# power_adc_module.net
KiCad netlist of a schematic drawn in EAGLE
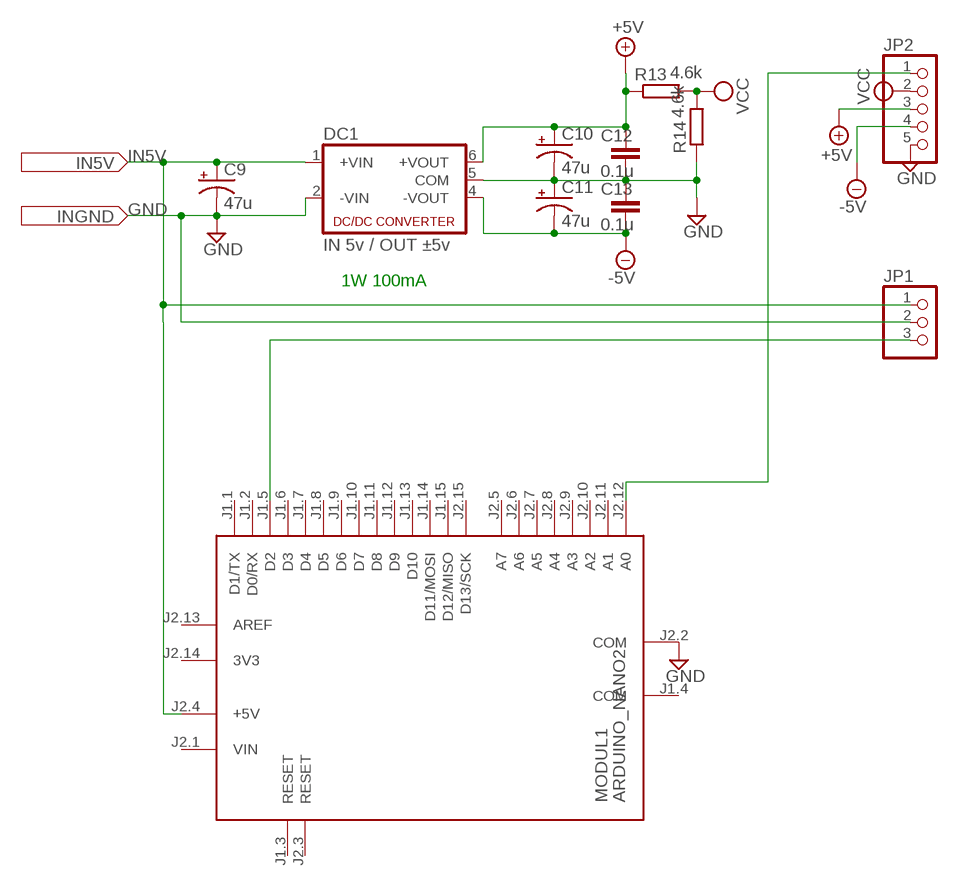
[diagram p0: schematic, sheet 1]

(export (version "E")
  (design (tool "Eeschema 10.0.6"))
  (components
    (comp (ref "C9")
      (value "47u")
      (footprint "eagle-import:E2,5-5")
      (libsource (lib "eagle-import") (part "CPOL-USE2.5-5"))
    )
    (comp (ref "C10")
      (value "47u")
      (footprint "eagle-import:E2,5-5")
      (libsource (lib "eagle-import") (part "CPOL-USE2.5-5"))
    )
    (comp (ref "C11")
      (value "47u")
      (footprint "eagle-import:E2,5-5")
      (libsource (lib "eagle-import") (part "CPOL-USE2.5-5"))
    )
    (comp (ref "C12")
      (value "0.1u")
      (footprint "eagle-import:C025-024X044")
      (libsource (lib "eagle-import") (part "C-EU025-024X044"))
    )
    (comp (ref "C13")
      (value "0.1u")
      (footprint "eagle-import:C025-024X044")
      (libsource (lib "eagle-import") (part "C-EU025-024X044"))
    )
    (comp (ref "DC1")
      (value "IN 5v / OUT ±5v")
      (footprint "eagle-import:NMA")
      (fields (field (name "MF") "C & D TECHNOLOGIES, INC") (field (name "MPN") "NMA0515SC"))
      (libsource (lib "eagle-import") (part "NMA"))
    )
    (comp (ref "JP1")
      (value "PINHD-1X3")
      (footprint "eagle-import:1X03")
      (libsource (lib "eagle-import") (part "PINHD-1X3"))
    )
    (comp (ref "JP2")
      (value "PINHD-1X5")
      (footprint "eagle-import:1X05")
      (libsource (lib "eagle-import") (part "PINHD-1X5"))
    )
    (comp (ref "MODUL1")
      (value "ARDUINO_NANO2")
      (footprint "eagle-import:ARDUINO_NANO2")
      (libsource (lib "eagle-import") (part "ARDUINO_NANO2"))
    )
    (comp (ref "R13")
      (value "4.6k")
      (footprint "eagle-import:0204_7")
      (libsource (lib "eagle-import") (part "R-EU_0204/7"))
    )
    (comp (ref "R14")
      (value "4.6k")
      (footprint "eagle-import:0204_7")
      (libsource (lib "eagle-import") (part "R-EU_0204/7"))
    )
  )
  (nets
    (net (code "1") (name "+5V") (class "Default")
      (node (ref "C10") (pin "+") (pinfunction "+_+") (pintype "passive"))
      (node (ref "C12") (pin "1") (pinfunction "1_1") (pintype "passive"))
      (node (ref "DC1") (pin "6") (pinfunction "+VOUT_6") (pintype "passive"))
      (node (ref "JP2") (pin "3") (pinfunction "3_3") (pintype "passive"))
      (node (ref "R13") (pin "1") (pinfunction "1_1") (pintype "passive"))
    )
    (net (code "2") (name "-5V") (class "Default")
      (node (ref "C11") (pin "-") (pinfunction "-_-") (pintype "passive"))
      (node (ref "C13") (pin "2") (pinfunction "2_2") (pintype "passive"))
      (node (ref "DC1") (pin "4") (pinfunction "-VOUT_4") (pintype "passive"))
      (node (ref "JP2") (pin "4") (pinfunction "4_4") (pintype "passive"))
    )
    (net (code "3") (name "/3V3") (class "Default")
      (node (ref "MODUL1") (pin "J2.14") (pinfunction "3V3_J2.14") (pintype "power_in"))
    )
    (net (code "4") (name "/AREF") (class "Default")
      (node (ref "MODUL1") (pin "J2.13") (pinfunction "AREF_J2.13") (pintype "power_in"))
    )
    (net (code "5") (name "/COM") (class "Default")
      (node (ref "MODUL1") (pin "J1.4") (pinfunction "COM_J1.4") (pintype "power_in"))
    )
    (net (code "6") (name "/IN5V") (class "Default")
      (node (ref "C9") (pin "+") (pinfunction "+_+") (pintype "passive"))
      (node (ref "DC1") (pin "1") (pinfunction "+VIN_1") (pintype "passive"))
      (node (ref "JP1") (pin "1") (pinfunction "1_1") (pintype "passive"))
      (node (ref "MODUL1") (pin "J2.4") (pinfunction "+5V_J2.4") (pintype "power_in"))
    )
    (net (code "7") (name "/VIN") (class "Default")
      (node (ref "MODUL1") (pin "J2.1") (pinfunction "VIN_J2.1") (pintype "power_in"))
    )
    (net (code "8") (name "GND") (class "Default")
      (node (ref "C10") (pin "-") (pinfunction "-_-") (pintype "passive"))
      (node (ref "C11") (pin "+") (pinfunction "+_+") (pintype "passive"))
      (node (ref "C12") (pin "2") (pinfunction "2_2") (pintype "passive"))
      (node (ref "C13") (pin "1") (pinfunction "1_1") (pintype "passive"))
      (node (ref "C9") (pin "-") (pinfunction "-_-") (pintype "passive"))
      (node (ref "DC1") (pin "2") (pinfunction "-VIN_2") (pintype "passive"))
      (node (ref "DC1") (pin "5") (pinfunction "COM_5") (pintype "passive"))
      (node (ref "JP1") (pin "2") (pinfunction "2_2") (pintype "passive"))
      (node (ref "JP2") (pin "5") (pinfunction "5_5") (pintype "passive"))
      (node (ref "MODUL1") (pin "J2.2") (pinfunction "COM_J2.2") (pintype "power_in"))
      (node (ref "R14") (pin "1") (pinfunction "1_1") (pintype "passive"))
    )
    (net (code "9") (name "Net-(MODUL1-A0)") (class "Default")
      (node (ref "JP2") (pin "1") (pinfunction "1_1") (pintype "passive"))
      (node (ref "MODUL1") (pin "J2.12") (pinfunction "A0_J2.12") (pintype "bidirectional"))
    )
    (net (code "10") (name "Net-(MODUL1-D2)") (class "Default")
      (node (ref "JP1") (pin "3") (pinfunction "3_3") (pintype "passive"))
      (node (ref "MODUL1") (pin "J1.5") (pinfunction "D2_J1.5") (pintype "bidirectional"))
    )
    (net (code "11") (name "VCC") (class "Default")
      (node (ref "JP2") (pin "2") (pinfunction "2_2") (pintype "passive"))
      (node (ref "R13") (pin "2") (pinfunction "2_2") (pintype "passive"))
      (node (ref "R14") (pin "2") (pinfunction "2_2") (pintype "passive"))
    )
    (net (code "12") (name "unconnected-(MODUL1-A1-PadJ2.11)") (class "Default")
      (node (ref "MODUL1") (pin "J2.11") (pinfunction "A1_J2.11") (pintype "bidirectional"))
    )
    (net (code "13") (name "unconnected-(MODUL1-A2-PadJ2.10)") (class "Default")
      (node (ref "MODUL1") (pin "J2.10") (pinfunction "A2_J2.10") (pintype "bidirectional"))
    )
    (net (code "14") (name "unconnected-(MODUL1-A3-PadJ2.9)") (class "Default")
      (node (ref "MODUL1") (pin "J2.9") (pinfunction "A3_J2.9") (pintype "bidirectional"))
    )
    (net (code "15") (name "unconnected-(MODUL1-A4-PadJ2.8)") (class "Default")
      (node (ref "MODUL1") (pin "J2.8") (pinfunction "A4_J2.8") (pintype "bidirectional"))
    )
    (net (code "16") (name "unconnected-(MODUL1-A5-PadJ2.7)") (class "Default")
      (node (ref "MODUL1") (pin "J2.7") (pinfunction "A5_J2.7") (pintype "bidirectional"))
    )
    (net (code "17") (name "unconnected-(MODUL1-A6-PadJ2.6)") (class "Default")
      (node (ref "MODUL1") (pin "J2.6") (pinfunction "A6_J2.6") (pintype "bidirectional"))
    )
    (net (code "18") (name "unconnected-(MODUL1-A7-PadJ2.5)") (class "Default")
      (node (ref "MODUL1") (pin "J2.5") (pinfunction "A7_J2.5") (pintype "bidirectional"))
    )
    (net (code "19") (name "unconnected-(MODUL1-D0{slash}RX-PadJ1.2)") (class "Default")
      (node (ref "MODUL1") (pin "J1.2") (pinfunction "D0/RX_J1.2") (pintype "bidirectional"))
    )
    (net (code "20") (name "unconnected-(MODUL1-D1{slash}TX-PadJ1.1)") (class "Default")
      (node (ref "MODUL1") (pin "J1.1") (pinfunction "D1/TX_J1.1") (pintype "bidirectional"))
    )
    (net (code "21") (name "unconnected-(MODUL1-D3-PadJ1.6)") (class "Default")
      (node (ref "MODUL1") (pin "J1.6") (pinfunction "D3_J1.6") (pintype "bidirectional"))
    )
    (net (code "22") (name "unconnected-(MODUL1-D4-PadJ1.7)") (class "Default")
      (node (ref "MODUL1") (pin "J1.7") (pinfunction "D4_J1.7") (pintype "bidirectional"))
    )
    (net (code "23") (name "unconnected-(MODUL1-D5-PadJ1.8)") (class "Default")
      (node (ref "MODUL1") (pin "J1.8") (pinfunction "D5_J1.8") (pintype "bidirectional"))
    )
    (net (code "24") (name "unconnected-(MODUL1-D6-PadJ1.9)") (class "Default")
      (node (ref "MODUL1") (pin "J1.9") (pinfunction "D6_J1.9") (pintype "bidirectional"))
    )
    (net (code "25") (name "unconnected-(MODUL1-D7-PadJ1.10)") (class "Default")
      (node (ref "MODUL1") (pin "J1.10") (pinfunction "D7_J1.10") (pintype "bidirectional"))
    )
    (net (code "26") (name "unconnected-(MODUL1-D8-PadJ1.11)") (class "Default")
      (node (ref "MODUL1") (pin "J1.11") (pinfunction "D8_J1.11") (pintype "bidirectional"))
    )
    (net (code "27") (name "unconnected-(MODUL1-D9-PadJ1.12)") (class "Default")
      (node (ref "MODUL1") (pin "J1.12") (pinfunction "D9_J1.12") (pintype "bidirectional"))
    )
    (net (code "28") (name "unconnected-(MODUL1-D10-PadJ1.13)") (class "Default")
      (node (ref "MODUL1") (pin "J1.13") (pinfunction "D10_J1.13") (pintype "bidirectional"))
    )
    (net (code "29") (name "unconnected-(MODUL1-D11{slash}MOSI-PadJ1.14)") (class "Default")
      (node (ref "MODUL1") (pin "J1.14") (pinfunction "D11/MOSI_J1.14") (pintype "bidirectional"))
    )
    (net (code "30") (name "unconnected-(MODUL1-D12{slash}MISO-PadJ1.15)") (class "Default")
      (node (ref "MODUL1") (pin "J1.15") (pinfunction "D12/MISO_J1.15") (pintype "bidirectional"))
    )
    (net (code "31") (name "unconnected-(MODUL1-D13{slash}SCK-PadJ2.15)") (class "Default")
      (node (ref "MODUL1") (pin "J2.15") (pinfunction "D13/SCK_J2.15") (pintype "bidirectional"))
    )
    (net (code "32") (name "unconnected-(MODUL1-RESET-PadJ1.3)") (class "Default")
      (node (ref "MODUL1") (pin "J1.3") (pinfunction "RESET_J1.3") (pintype "bidirectional"))
    )
    (net (code "33") (name "unconnected-(MODUL1-RESET-PadJ2.3)") (class "Default")
      (node (ref "MODUL1") (pin "J2.3") (pinfunction "RESET_J2.3") (pintype "bidirectional"))
    )
  )
)
